# schematic.net
KiCad netlist of a schematic drawn in EAGLE
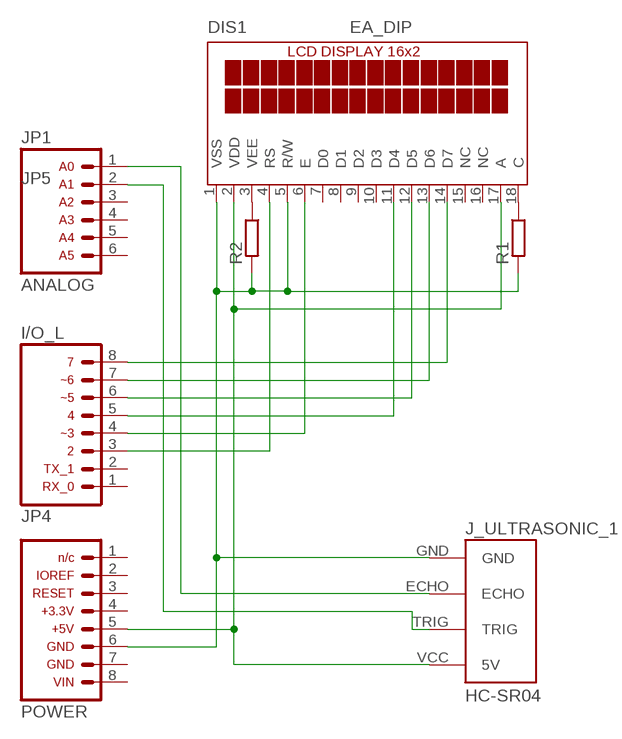
[diagram p0: schematic, sheet 1]

(export (version "E")
  (design (tool "Eeschema 10.0.6"))
  (components
    (comp (ref "DIS1")
      (value "EA_DIP")
      (footprint "eagle-import:EA_DIP")
      (libsource (lib "eagle-import") (part "EA_DIP"))
    )
    (comp (ref "JP1")
      (value "ARDUINO_CONN-ANALOGSIP")
      (footprint "eagle-import:CONN-1X06")
      (libsource (lib "eagle-import") (part "ARDUINO_CONN-ANALOGSIP"))
    )
    (comp (ref "JP4")
      (value "ARDUINO_CONN-IO_LSIP")
      (footprint "eagle-import:CONN-1X08")
      (libsource (lib "eagle-import") (part "ARDUINO_CONN-IO_LSIP"))
    )
    (comp (ref "JP5")
      (value "ARDUINO_CONN-POWERSIP")
      (footprint "eagle-import:CONN-1X08")
      (libsource (lib "eagle-import") (part "ARDUINO_CONN-POWERSIP"))
    )
    (comp (ref "J_ULTRASONIC_1")
      (value "HC-SR04")
      (footprint "eagle-import:HC-SR04_FOOTPRINT")
      (libsource (lib "eagle-import") (part "HC-SR04"))
    )
    (comp (ref "R1")
      (value "PMD")
      (footprint "eagle-import:PMD")
      (libsource (lib "eagle-import") (part "PMD"))
    )
    (comp (ref "R2")
      (value "PMD")
      (footprint "eagle-import:PMD")
      (libsource (lib "eagle-import") (part "PMD"))
    )
  )
  (nets
    (net (code "1") (name "Net-(DIS1-A)") (class "Default")
      (node (ref "DIS1") (pin "17") (pinfunction "A_17") (pintype "passive"))
      (node (ref "DIS1") (pin "2") (pinfunction "VDD_2") (pintype "power_in"))
      (node (ref "JP5") (pin "5") (pinfunction "5_5") (pintype "passive"))
      (node (ref "J_ULTRASONIC_1") (pin "VCC") (pinfunction "5V_VCC") (pintype "bidirectional"))
    )
    (net (code "2") (name "Net-(DIS1-C)") (class "Default")
      (node (ref "DIS1") (pin "18") (pinfunction "C_18") (pintype "passive"))
      (node (ref "R1") (pin "1") (pinfunction "1_1") (pintype "passive"))
    )
    (net (code "3") (name "Net-(DIS1-D4)") (class "Default")
      (node (ref "DIS1") (pin "11") (pinfunction "D4_11") (pintype "input"))
      (node (ref "JP4") (pin "5") (pinfunction "5_5") (pintype "passive"))
    )
    (net (code "4") (name "Net-(DIS1-D5)") (class "Default")
      (node (ref "DIS1") (pin "12") (pinfunction "D5_12") (pintype "input"))
      (node (ref "JP4") (pin "6") (pinfunction "6_6") (pintype "passive"))
    )
    (net (code "5") (name "Net-(DIS1-D6)") (class "Default")
      (node (ref "DIS1") (pin "13") (pinfunction "D6_13") (pintype "input"))
      (node (ref "JP4") (pin "7") (pinfunction "7_7") (pintype "passive"))
    )
    (net (code "6") (name "Net-(DIS1-D7)") (class "Default")
      (node (ref "DIS1") (pin "14") (pinfunction "D7_14") (pintype "input"))
      (node (ref "JP4") (pin "8") (pinfunction "8_8") (pintype "passive"))
    )
    (net (code "7") (name "Net-(DIS1-E)") (class "Default")
      (node (ref "DIS1") (pin "6") (pinfunction "E_6") (pintype "input"))
      (node (ref "JP4") (pin "4") (pinfunction "4_4") (pintype "passive"))
    )
    (net (code "8") (name "Net-(DIS1-RS)") (class "Default")
      (node (ref "DIS1") (pin "4") (pinfunction "RS_4") (pintype "input"))
      (node (ref "JP4") (pin "3") (pinfunction "3_3") (pintype "passive"))
    )
    (net (code "9") (name "Net-(DIS1-R{slash}W)") (class "Default")
      (node (ref "DIS1") (pin "1") (pinfunction "VSS_1") (pintype "power_in"))
      (node (ref "DIS1") (pin "5") (pinfunction "R/W_5") (pintype "input"))
      (node (ref "JP5") (pin "6") (pinfunction "6_6") (pintype "passive"))
      (node (ref "J_ULTRASONIC_1") (pin "GND") (pinfunction "GND_GND") (pintype "bidirectional"))
      (node (ref "R1") (pin "2") (pinfunction "2_2") (pintype "passive"))
      (node (ref "R2") (pin "2") (pinfunction "2_2") (pintype "passive"))
    )
    (net (code "10") (name "Net-(DIS1-VEE)") (class "Default")
      (node (ref "DIS1") (pin "3") (pinfunction "VEE_3") (pintype "power_in"))
      (node (ref "R2") (pin "1") (pinfunction "1_1") (pintype "passive"))
    )
    (net (code "11") (name "Net-(JP1-Pad1)") (class "Default")
      (node (ref "JP1") (pin "1") (pinfunction "1_1") (pintype "passive"))
      (node (ref "J_ULTRASONIC_1") (pin "ECHO") (pinfunction "ECHO_ECHO") (pintype "bidirectional"))
    )
    (net (code "12") (name "Net-(JP1-Pad2)") (class "Default")
      (node (ref "JP1") (pin "2") (pinfunction "2_2") (pintype "passive"))
      (node (ref "J_ULTRASONIC_1") (pin "TRIG") (pinfunction "TRIG_TRIG") (pintype "bidirectional"))
    )
    (net (code "13") (name "unconnected-(DIS1-D0-Pad7)") (class "Default")
      (node (ref "DIS1") (pin "7") (pinfunction "D0_7") (pintype "input"))
    )
    (net (code "14") (name "unconnected-(DIS1-D1-Pad8)") (class "Default")
      (node (ref "DIS1") (pin "8") (pinfunction "D1_8") (pintype "input"))
    )
    (net (code "15") (name "unconnected-(DIS1-D2-Pad9)") (class "Default")
      (node (ref "DIS1") (pin "9") (pinfunction "D2_9") (pintype "input"))
    )
    (net (code "16") (name "unconnected-(DIS1-D3-Pad10)") (class "Default")
      (node (ref "DIS1") (pin "10") (pinfunction "D3_10") (pintype "input"))
    )
    (net (code "17") (name "unconnected-(DIS1-NC-Pad15)") (class "Default")
      (node (ref "DIS1") (pin "15") (pinfunction "NC_15") (pintype "no_connect"))
    )
    (net (code "18") (name "unconnected-(DIS1-NC-Pad16)") (class "Default")
      (node (ref "DIS1") (pin "16") (pinfunction "NC_16") (pintype "no_connect"))
    )
    (net (code "19") (name "unconnected-(JP1-Pad3)") (class "Default")
      (node (ref "JP1") (pin "3") (pinfunction "3_3") (pintype "passive"))
    )
    (net (code "20") (name "unconnected-(JP1-Pad4)") (class "Default")
      (node (ref "JP1") (pin "4") (pinfunction "4_4") (pintype "passive"))
    )
    (net (code "21") (name "unconnected-(JP1-Pad5)") (class "Default")
      (node (ref "JP1") (pin "5") (pinfunction "5_5") (pintype "passive"))
    )
    (net (code "22") (name "unconnected-(JP1-Pad6)") (class "Default")
      (node (ref "JP1") (pin "6") (pinfunction "6_6") (pintype "passive"))
    )
    (net (code "23") (name "unconnected-(JP4-Pad1)") (class "Default")
      (node (ref "JP4") (pin "1") (pinfunction "1_1") (pintype "passive"))
    )
    (net (code "24") (name "unconnected-(JP4-Pad2)") (class "Default")
      (node (ref "JP4") (pin "2") (pinfunction "2_2") (pintype "passive"))
    )
    (net (code "25") (name "unconnected-(JP5-Pad1)") (class "Default")
      (node (ref "JP5") (pin "1") (pinfunction "1_1") (pintype "passive"))
    )
    (net (code "26") (name "unconnected-(JP5-Pad2)") (class "Default")
      (node (ref "JP5") (pin "2") (pinfunction "2_2") (pintype "passive"))
    )
    (net (code "27") (name "unconnected-(JP5-Pad3)") (class "Default")
      (node (ref "JP5") (pin "3") (pinfunction "3_3") (pintype "passive"))
    )
    (net (code "28") (name "unconnected-(JP5-Pad4)") (class "Default")
      (node (ref "JP5") (pin "4") (pinfunction "4_4") (pintype "passive"))
    )
    (net (code "29") (name "unconnected-(JP5-Pad7)") (class "Default")
      (node (ref "JP5") (pin "7") (pinfunction "7_7") (pintype "passive"))
    )
    (net (code "30") (name "unconnected-(JP5-Pad8)") (class "Default")
      (node (ref "JP5") (pin "8") (pinfunction "8_8") (pintype "passive"))
    )
  )
)
